# Mutatio_REV1.net
KiCad netlist of a schematic drawn in EAGLE
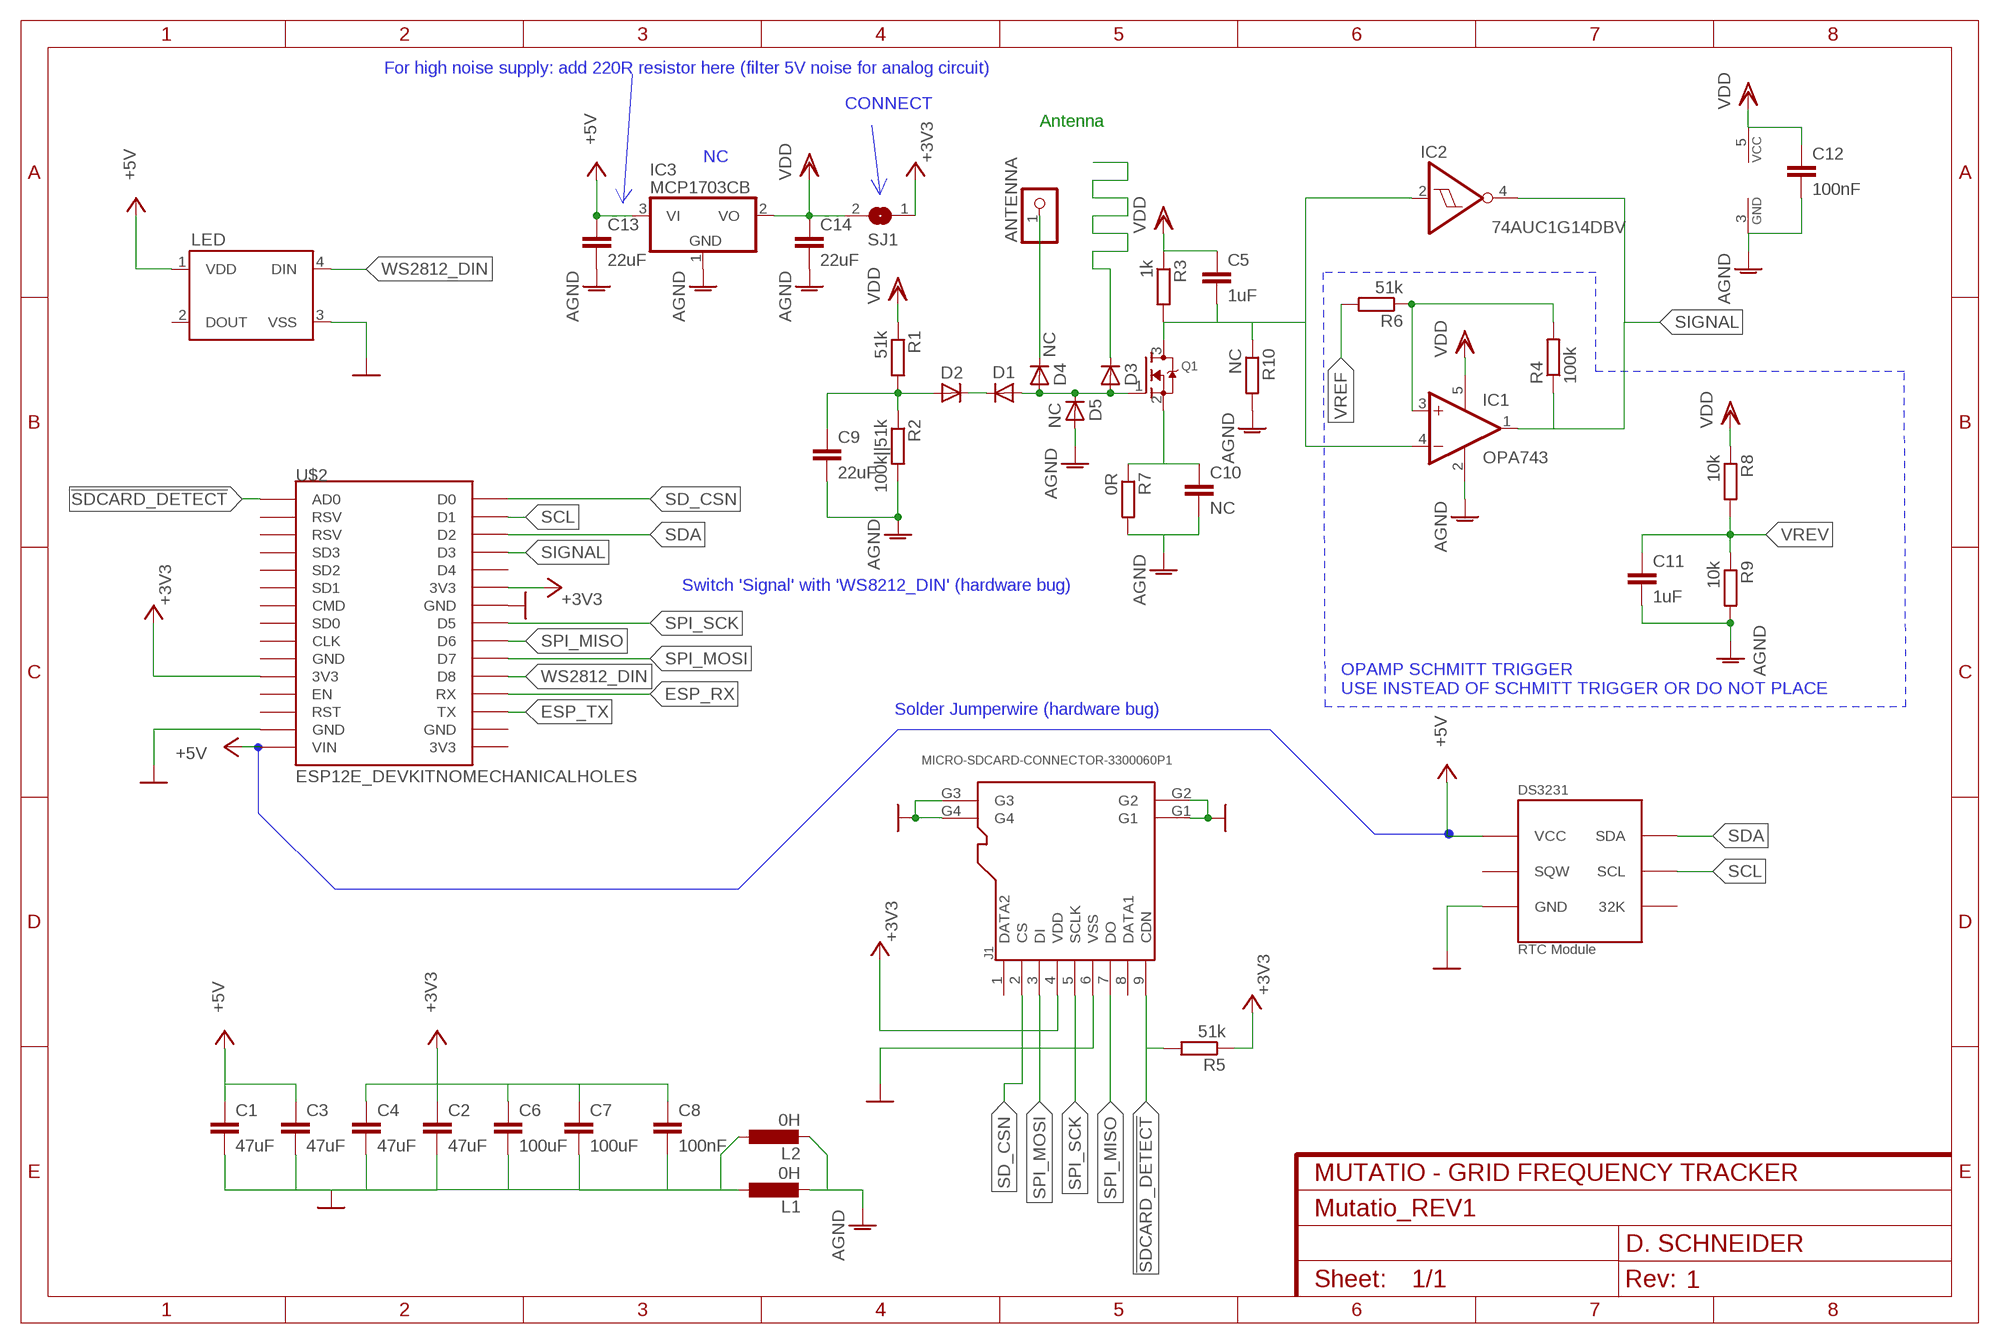
[diagram p0: schematic, sheet 1]

(export (version "E")
  (design (tool "Eeschema 10.0.6"))
  (components
    (comp (ref "ANTENNA")
      (value "PINHD-1X1CB")
      (footprint "eagle-import:1X01-CLEANBIG")
      (libsource (lib "eagle-import") (part "PINHD-1X1CB"))
    )
    (comp (ref "C1")
      (value "47uF")
      (footprint "eagle-import:C0805")
      (libsource (lib "eagle-import") (part "C-EUC0805"))
    )
    (comp (ref "C2")
      (value "47uF")
      (footprint "eagle-import:C0805")
      (libsource (lib "eagle-import") (part "C-EUC0805"))
    )
    (comp (ref "C3")
      (value "47uF")
      (footprint "eagle-import:C0805")
      (libsource (lib "eagle-import") (part "C-EUC0805"))
    )
    (comp (ref "C4")
      (value "47uF")
      (footprint "eagle-import:C0805")
      (libsource (lib "eagle-import") (part "C-EUC0805"))
    )
    (comp (ref "C5")
      (value "1uF")
      (footprint "eagle-import:C0603")
      (libsource (lib "eagle-import") (part "C-EUC0603"))
    )
    (comp (ref "C6")
      (value "100uF")
      (footprint "eagle-import:C1206")
      (libsource (lib "eagle-import") (part "C-EUC1206"))
    )
    (comp (ref "C7")
      (value "100uF")
      (footprint "eagle-import:C1206")
      (libsource (lib "eagle-import") (part "C-EUC1206"))
    )
    (comp (ref "C8")
      (value "100nF")
      (footprint "eagle-import:C0603")
      (libsource (lib "eagle-import") (part "C-EUC0603"))
    )
    (comp (ref "C9")
      (value "22uF")
      (footprint "eagle-import:C0603")
      (libsource (lib "eagle-import") (part "C-EUC0603"))
    )
    (comp (ref "C10")
      (value "NC")
      (footprint "eagle-import:C0603")
      (libsource (lib "eagle-import") (part "C-EUC0603"))
    )
    (comp (ref "C11")
      (value "1uF")
      (footprint "eagle-import:C0603")
      (libsource (lib "eagle-import") (part "C-EUC0603"))
    )
    (comp (ref "C12")
      (value "100nF")
      (footprint "eagle-import:C0603")
      (libsource (lib "eagle-import") (part "C-EUC0603"))
    )
    (comp (ref "C13")
      (value "22uF")
      (footprint "eagle-import:C0603")
      (libsource (lib "eagle-import") (part "C-EUC0603"))
    )
    (comp (ref "C14")
      (value "22uF")
      (footprint "eagle-import:C0603")
      (libsource (lib "eagle-import") (part "C-EUC0603"))
    )
    (comp (ref "D1")
      (value "DIODE-MINIMELF")
      (footprint "eagle-import:MINIMELF")
      (libsource (lib "eagle-import") (part "DIODE-MINIMELF"))
    )
    (comp (ref "D2")
      (value "DIODE-MINIMELF")
      (footprint "eagle-import:MINIMELF")
      (libsource (lib "eagle-import") (part "DIODE-MINIMELF"))
    )
    (comp (ref "D3")
      (value "DIODE-MINIMELF")
      (footprint "eagle-import:MINIMELF")
      (libsource (lib "eagle-import") (part "DIODE-MINIMELF"))
    )
    (comp (ref "D4")
      (value "NC")
      (footprint "eagle-import:MINIMELF")
      (libsource (lib "eagle-import") (part "DIODE-MINIMELF"))
    )
    (comp (ref "D5")
      (value "NC")
      (footprint "eagle-import:MINIMELF")
      (libsource (lib "eagle-import") (part "DIODE-MINIMELF"))
    )
    (comp (ref "IC1")
      (value "OPA743")
      (footprint "eagle-import:SOT23-5")
      (libsource (lib "eagle-import") (part "OPA743"))
    )
    (comp (ref "IC2")
      (value "74AUC1G14DBV")
      (footprint "eagle-import:SOT23-5")
      (libsource (lib "eagle-import") (part "741G14DBVAUC"))
    )
    (comp (ref "IC3")
      (value "MCP1703CB")
      (footprint "eagle-import:SOT23")
      (libsource (lib "eagle-import") (part "MCP1703CB"))
    )
    (comp (ref "J1")
      (value "MICRO-SDCARD-CONNECTOR-3300060P1")
      (footprint "eagle-import:9P-SMD-W-RING")
      (libsource (lib "eagle-import") (part "MICRO-SDCARD-CONNECTOR-3300060P1"))
    )
    (comp (ref "L1")
      (value "0H")
      (footprint "eagle-import:L2012C")
      (libsource (lib "eagle-import") (part "L-EUL2012C"))
    )
    (comp (ref "L2")
      (value "0H")
      (footprint "eagle-import:L2012C")
      (libsource (lib "eagle-import") (part "L-EUL2012C"))
    )
    (comp (ref "LED")
      (value "WS2812B")
      (footprint "eagle-import:WS2812B")
      (libsource (lib "eagle-import") (part "WS2812B"))
    )
    (comp (ref "Q1")
      (value "MOSFET-NREFLOW")
      (footprint "eagle-import:SOT23")
      (libsource (lib "eagle-import") (part "MOSFET-NREFLOW"))
    )
    (comp (ref "R1")
      (value "51k")
      (footprint "eagle-import:R0603")
      (libsource (lib "eagle-import") (part "R-EU_R0603"))
    )
    (comp (ref "R2")
      (value "100k||51k")
      (footprint "eagle-import:R0603")
      (libsource (lib "eagle-import") (part "R-EU_R0603"))
    )
    (comp (ref "R3")
      (value "1k")
      (footprint "eagle-import:R0603")
      (libsource (lib "eagle-import") (part "R-EU_R0603"))
    )
    (comp (ref "R4")
      (value "100k")
      (footprint "eagle-import:R0603")
      (libsource (lib "eagle-import") (part "R-EU_R0603"))
    )
    (comp (ref "R5")
      (value "51k")
      (footprint "eagle-import:R0603")
      (libsource (lib "eagle-import") (part "R-EU_R0603"))
    )
    (comp (ref "R6")
      (value "51k")
      (footprint "eagle-import:R0603")
      (libsource (lib "eagle-import") (part "R-EU_R0603"))
    )
    (comp (ref "R7")
      (value "0R")
      (footprint "eagle-import:R0603")
      (libsource (lib "eagle-import") (part "R-EU_R0603"))
    )
    (comp (ref "R8")
      (value "10k")
      (footprint "eagle-import:R0603")
      (libsource (lib "eagle-import") (part "R-EU_R0603"))
    )
    (comp (ref "R9")
      (value "10k")
      (footprint "eagle-import:R0603")
      (libsource (lib "eagle-import") (part "R-EU_R0603"))
    )
    (comp (ref "R10")
      (value "NC")
      (footprint "eagle-import:R0603")
      (libsource (lib "eagle-import") (part "R-EU_R0603"))
    )
    (comp (ref "SJ1") (value "SJ") (footprint "eagle-import:SJ") (libsource (lib "eagle-import") (part "SJ")))
    (comp (ref "U$1")
      (value "DS3231_MODULEBIG_CONNECTER_ONLY")
      (footprint "eagle-import:DS3231_MODULE_BIGCON")
      (libsource (lib "eagle-import") (part "DS3231_MODULEBIG_CONNECTER_ONLY"))
    )
    (comp (ref "U$2")
      (value "ESP12E_DEVKITNOMECHANICALHOLES")
      (footprint "eagle-import:ESP12E_DEVKIT_NOHOLES")
      (libsource (lib "eagle-import") (part "ESP12E_DEVKITNOMECHANICALHOLES"))
    )
  )
  (nets
    (net (code "1") (name "+3V3") (class "Default")
      (node (ref "C2") (pin "1") (pinfunction "1_1") (pintype "passive"))
      (node (ref "C4") (pin "1") (pinfunction "1_1") (pintype "passive"))
      (node (ref "C6") (pin "1") (pinfunction "1_1") (pintype "passive"))
      (node (ref "C7") (pin "1") (pinfunction "1_1") (pintype "passive"))
      (node (ref "C8") (pin "1") (pinfunction "1_1") (pintype "passive"))
      (node (ref "J1") (pin "4") (pinfunction "VDD_4") (pintype "bidirectional"))
      (node (ref "R5") (pin "1") (pinfunction "1_1") (pintype "passive"))
      (node (ref "SJ1") (pin "1") (pinfunction "1_1") (pintype "passive"))
      (node (ref "U$2") (pin "3V3@0") (pinfunction "3V3_3V3@0") (pintype "bidirectional"))
      (node (ref "U$2") (pin "3V3@1") (pinfunction "3V3_3V3@1") (pintype "bidirectional"))
    )
    (net (code "2") (name "+5V") (class "Default")
      (node (ref "C1") (pin "1") (pinfunction "1_1") (pintype "passive"))
      (node (ref "C13") (pin "1") (pinfunction "1_1") (pintype "passive"))
      (node (ref "C3") (pin "1") (pinfunction "1_1") (pintype "passive"))
      (node (ref "IC3") (pin "3") (pinfunction "VI_3") (pintype "input"))
      (node (ref "LED") (pin "1") (pinfunction "VDD_1") (pintype "power_in"))
      (node (ref "U$1") (pin "VCC@2") (pinfunction "VCC_VCC@2") (pintype "bidirectional"))
      (node (ref "U$2") (pin "VIN") (pinfunction "VIN_VIN") (pintype "bidirectional"))
    )
    (net (code "3") (name "/~{SDCARD_DETECT}") (class "Default")
      (node (ref "J1") (pin "9") (pinfunction "CDN_9") (pintype "bidirectional"))
      (node (ref "R5") (pin "2") (pinfunction "2_2") (pintype "passive"))
      (node (ref "U$2") (pin "AD0") (pinfunction "AD0_AD0") (pintype "bidirectional"))
    )
    (net (code "4") (name "AGND") (class "Default")
      (node (ref "C10") (pin "2") (pinfunction "2_2") (pintype "passive"))
      (node (ref "C11") (pin "2") (pinfunction "2_2") (pintype "passive"))
      (node (ref "C12") (pin "2") (pinfunction "2_2") (pintype "passive"))
      (node (ref "C13") (pin "2") (pinfunction "2_2") (pintype "passive"))
      (node (ref "C14") (pin "2") (pinfunction "2_2") (pintype "passive"))
      (node (ref "C9") (pin "2") (pinfunction "2_2") (pintype "passive"))
      (node (ref "D5") (pin "A") (pinfunction "A_A") (pintype "passive"))
      (node (ref "IC1") (pin "2") (pinfunction "V-_2") (pintype "power_in"))
      (node (ref "IC2") (pin "3") (pinfunction "GND_3") (pintype "power_in"))
      (node (ref "IC3") (pin "1") (pinfunction "GND_1") (pintype "passive"))
      (node (ref "L1") (pin "2") (pinfunction "2_2") (pintype "passive"))
      (node (ref "L2") (pin "2") (pinfunction "2_2") (pintype "passive"))
      (node (ref "R10") (pin "2") (pinfunction "2_2") (pintype "passive"))
      (node (ref "R2") (pin "2") (pinfunction "2_2") (pintype "passive"))
      (node (ref "R7") (pin "2") (pinfunction "2_2") (pintype "passive"))
      (node (ref "R9") (pin "2") (pinfunction "2_2") (pintype "passive"))
    )
    (net (code "5") (name "ESP_RX") (class "Default")
      (node (ref "U$2") (pin "RX") (pinfunction "RX_RX") (pintype "bidirectional"))
    )
    (net (code "6") (name "ESP_TX") (class "Default")
      (node (ref "U$2") (pin "TX") (pinfunction "TX_TX") (pintype "bidirectional"))
    )
    (net (code "7") (name "GND") (class "Default")
      (node (ref "C1") (pin "2") (pinfunction "2_2") (pintype "passive"))
      (node (ref "C2") (pin "2") (pinfunction "2_2") (pintype "passive"))
      (node (ref "C3") (pin "2") (pinfunction "2_2") (pintype "passive"))
      (node (ref "C4") (pin "2") (pinfunction "2_2") (pintype "passive"))
      (node (ref "C6") (pin "2") (pinfunction "2_2") (pintype "passive"))
      (node (ref "C7") (pin "2") (pinfunction "2_2") (pintype "passive"))
      (node (ref "C8") (pin "2") (pinfunction "2_2") (pintype "passive"))
      (node (ref "J1") (pin "6") (pinfunction "VSS_6") (pintype "bidirectional"))
      (node (ref "J1") (pin "G1") (pinfunction "G1_G1") (pintype "bidirectional"))
      (node (ref "J1") (pin "G2") (pinfunction "G2_G2") (pintype "bidirectional"))
      (node (ref "J1") (pin "G3") (pinfunction "G3_G3") (pintype "bidirectional"))
      (node (ref "J1") (pin "G4") (pinfunction "G4_G4") (pintype "bidirectional"))
      (node (ref "L1") (pin "1") (pinfunction "1_1") (pintype "passive"))
      (node (ref "L2") (pin "1") (pinfunction "1_1") (pintype "passive"))
      (node (ref "LED") (pin "3") (pinfunction "VSS_3") (pintype "power_in"))
      (node (ref "U$1") (pin "GND@2") (pinfunction "GND_GND@2") (pintype "bidirectional"))
      (node (ref "U$2") (pin "GND@1") (pinfunction "GND_GND@1") (pintype "bidirectional"))
      (node (ref "U$2") (pin "GND@2") (pinfunction "GND_GND@2") (pintype "bidirectional"))
    )
    (net (code "8") (name "Net-(ANTENNA-Pad1)") (class "Default")
      (node (ref "ANTENNA") (pin "1") (pinfunction "1_1") (pintype "passive"))
      (node (ref "D4") (pin "C") (pinfunction "C_C") (pintype "passive"))
    )
    (net (code "9") (name "Net-(C9-Pad1)") (class "Default")
      (node (ref "C9") (pin "1") (pinfunction "1_1") (pintype "passive"))
      (node (ref "D2") (pin "A") (pinfunction "A_A") (pintype "passive"))
      (node (ref "R1") (pin "2") (pinfunction "2_2") (pintype "passive"))
      (node (ref "R2") (pin "1") (pinfunction "1_1") (pintype "passive"))
    )
    (net (code "10") (name "Net-(D1-PadC)") (class "Default")
      (node (ref "D1") (pin "C") (pinfunction "C_C") (pintype "passive"))
      (node (ref "D2") (pin "C") (pinfunction "C_C") (pintype "passive"))
    )
    (net (code "11") (name "Net-(IC1-+IN)") (class "Default")
      (node (ref "IC1") (pin "3") (pinfunction "+IN_3") (pintype "input"))
      (node (ref "R4") (pin "2") (pinfunction "2_2") (pintype "passive"))
      (node (ref "R6") (pin "1") (pinfunction "1_1") (pintype "passive"))
    )
    (net (code "12") (name "Net-(IC1--IN)") (class "Default")
      (node (ref "C5") (pin "2") (pinfunction "2_2") (pintype "passive"))
      (node (ref "IC1") (pin "4") (pinfunction "-IN_4") (pintype "input"))
      (node (ref "IC2") (pin "2") (pinfunction "I_2") (pintype "input"))
      (node (ref "Q1") (pin "3") (pinfunction "D_3") (pintype "bidirectional"))
      (node (ref "R10") (pin "1") (pinfunction "1_1") (pintype "passive"))
      (node (ref "R3") (pin "2") (pinfunction "2_2") (pintype "passive"))
    )
    (net (code "13") (name "Net-(Q1-G)") (class "Default")
      (node (ref "D1") (pin "A") (pinfunction "A_A") (pintype "passive"))
      (node (ref "D3") (pin "A") (pinfunction "A_A") (pintype "passive"))
      (node (ref "D4") (pin "A") (pinfunction "A_A") (pintype "passive"))
      (node (ref "D5") (pin "C") (pinfunction "C_C") (pintype "passive"))
      (node (ref "Q1") (pin "1") (pinfunction "G_1") (pintype "bidirectional"))
    )
    (net (code "14") (name "Net-(Q1-S)") (class "Default")
      (node (ref "C10") (pin "1") (pinfunction "1_1") (pintype "passive"))
      (node (ref "Q1") (pin "2") (pinfunction "S_2") (pintype "bidirectional"))
      (node (ref "R7") (pin "1") (pinfunction "1_1") (pintype "passive"))
    )
    (net (code "15") (name "SCL") (class "Default")
      (node (ref "U$1") (pin "SCL@2") (pinfunction "SCL_SCL@2") (pintype "bidirectional"))
      (node (ref "U$2") (pin "D1") (pinfunction "D1_D1") (pintype "bidirectional"))
    )
    (net (code "16") (name "SDA") (class "Default")
      (node (ref "U$1") (pin "SDA@2") (pinfunction "SDA_SDA@2") (pintype "bidirectional"))
      (node (ref "U$2") (pin "D2") (pinfunction "D2_D2") (pintype "bidirectional"))
    )
    (net (code "17") (name "SD_CSN") (class "Default")
      (node (ref "J1") (pin "2") (pinfunction "CS_2") (pintype "bidirectional"))
      (node (ref "U$2") (pin "D0") (pinfunction "D0_D0") (pintype "bidirectional"))
    )
    (net (code "18") (name "SIGNAL") (class "Default")
      (node (ref "IC1") (pin "1") (pinfunction "OUT_1") (pintype "output"))
      (node (ref "IC2") (pin "4") (pinfunction "O_4") (pintype "output"))
      (node (ref "R4") (pin "1") (pinfunction "1_1") (pintype "passive"))
      (node (ref "U$2") (pin "D3") (pinfunction "D3_D3") (pintype "bidirectional"))
    )
    (net (code "19") (name "SPI_MISO") (class "Default")
      (node (ref "J1") (pin "7") (pinfunction "DO_7") (pintype "bidirectional"))
      (node (ref "U$2") (pin "D6") (pinfunction "D6_D6") (pintype "bidirectional"))
    )
    (net (code "20") (name "SPI_MOSI") (class "Default")
      (node (ref "J1") (pin "3") (pinfunction "DI_3") (pintype "bidirectional"))
      (node (ref "U$2") (pin "D7") (pinfunction "D7_D7") (pintype "bidirectional"))
    )
    (net (code "21") (name "SPI_SCK") (class "Default")
      (node (ref "J1") (pin "5") (pinfunction "SCLK_5") (pintype "bidirectional"))
      (node (ref "U$2") (pin "D5") (pinfunction "D5_D5") (pintype "bidirectional"))
    )
    (net (code "22") (name "VDD") (class "Default")
      (node (ref "C12") (pin "1") (pinfunction "1_1") (pintype "passive"))
      (node (ref "C14") (pin "1") (pinfunction "1_1") (pintype "passive"))
      (node (ref "C5") (pin "1") (pinfunction "1_1") (pintype "passive"))
      (node (ref "IC1") (pin "5") (pinfunction "V+_5") (pintype "power_in"))
      (node (ref "IC2") (pin "5") (pinfunction "VCC_5") (pintype "power_in"))
      (node (ref "IC3") (pin "2") (pinfunction "VO_2") (pintype "passive"))
      (node (ref "R1") (pin "1") (pinfunction "1_1") (pintype "passive"))
      (node (ref "R3") (pin "1") (pinfunction "1_1") (pintype "passive"))
      (node (ref "R8") (pin "1") (pinfunction "1_1") (pintype "passive"))
      (node (ref "SJ1") (pin "2") (pinfunction "2_2") (pintype "passive"))
    )
    (net (code "23") (name "VREF") (class "Default")
      (node (ref "R6") (pin "2") (pinfunction "2_2") (pintype "passive"))
    )
    (net (code "24") (name "VREV") (class "Default")
      (node (ref "C11") (pin "1") (pinfunction "1_1") (pintype "passive"))
      (node (ref "R8") (pin "2") (pinfunction "2_2") (pintype "passive"))
      (node (ref "R9") (pin "1") (pinfunction "1_1") (pintype "passive"))
    )
    (net (code "25") (name "WS2812_DIN") (class "Default")
      (node (ref "LED") (pin "4") (pinfunction "DIN_4") (pintype "input"))
      (node (ref "U$2") (pin "D8") (pinfunction "D8_D8") (pintype "bidirectional"))
    )
    (net (code "26") (name "unconnected-(D3-PadC)") (class "Default")
      (node (ref "D3") (pin "C") (pinfunction "C_C") (pintype "passive"))
    )
    (net (code "27") (name "unconnected-(J1-DATA1-Pad8)") (class "Default")
      (node (ref "J1") (pin "8") (pinfunction "DATA1_8") (pintype "bidirectional"))
    )
    (net (code "28") (name "unconnected-(J1-DATA2-Pad1)") (class "Default")
      (node (ref "J1") (pin "1") (pinfunction "DATA2_1") (pintype "bidirectional"))
    )
    (net (code "29") (name "unconnected-(LED-DOUT-Pad2)") (class "Default")
      (node (ref "LED") (pin "2") (pinfunction "DOUT_2") (pintype "output"))
    )
    (net (code "30") (name "unconnected-(U$1-Pad32K)") (class "Default")
      (node (ref "U$1") (pin "32K") (pinfunction "32K_32K") (pintype "bidirectional"))
    )
    (net (code "31") (name "unconnected-(U$1-PadSQW)") (class "Default")
      (node (ref "U$1") (pin "SQW") (pinfunction "SQW_SQW") (pintype "bidirectional"))
    )
    (net (code "32") (name "unconnected-(U$2-3V3-Pad3V3@2)") (class "Default")
      (node (ref "U$2") (pin "3V3@2") (pinfunction "3V3_3V3@2") (pintype "bidirectional"))
    )
    (net (code "33") (name "unconnected-(U$2-GND-PadGND@0)") (class "Default")
      (node (ref "U$2") (pin "GND@0") (pinfunction "GND_GND@0") (pintype "bidirectional"))
    )
    (net (code "34") (name "unconnected-(U$2-GND-PadGND@3)") (class "Default")
      (node (ref "U$2") (pin "GND@3") (pinfunction "GND_GND@3") (pintype "bidirectional"))
    )
    (net (code "35") (name "unconnected-(U$2-PadCLK)") (class "Default")
      (node (ref "U$2") (pin "CLK") (pinfunction "CLK_CLK") (pintype "bidirectional"))
    )
    (net (code "36") (name "unconnected-(U$2-PadCMD)") (class "Default")
      (node (ref "U$2") (pin "CMD") (pinfunction "CMD_CMD") (pintype "bidirectional"))
    )
    (net (code "37") (name "unconnected-(U$2-PadD4)") (class "Default")
      (node (ref "U$2") (pin "D4") (pinfunction "D4_D4") (pintype "bidirectional"))
    )
    (net (code "38") (name "unconnected-(U$2-PadEN)") (class "Default")
      (node (ref "U$2") (pin "EN") (pinfunction "EN_EN") (pintype "bidirectional"))
    )
    (net (code "39") (name "unconnected-(U$2-PadRST)") (class "Default")
      (node (ref "U$2") (pin "RST") (pinfunction "RST_RST") (pintype "bidirectional"))
    )
    (net (code "40") (name "unconnected-(U$2-PadSD0)") (class "Default")
      (node (ref "U$2") (pin "SD0") (pinfunction "SD0_SD0") (pintype "bidirectional"))
    )
    (net (code "41") (name "unconnected-(U$2-PadSD1)") (class "Default")
      (node (ref "U$2") (pin "SD1") (pinfunction "SD1_SD1") (pintype "bidirectional"))
    )
    (net (code "42") (name "unconnected-(U$2-PadSD2)") (class "Default")
      (node (ref "U$2") (pin "SD2") (pinfunction "SD2_SD2") (pintype "bidirectional"))
    )
    (net (code "43") (name "unconnected-(U$2-PadSD3)") (class "Default")
      (node (ref "U$2") (pin "SD3") (pinfunction "SD3_SD3") (pintype "bidirectional"))
    )
    (net (code "44") (name "unconnected-(U$2-RSV-PadRSV@0)") (class "Default")
      (node (ref "U$2") (pin "RSV@0") (pinfunction "RSV_RSV@0") (pintype "bidirectional"))
    )
    (net (code "45") (name "unconnected-(U$2-RSV-PadRSV@1)") (class "Default")
      (node (ref "U$2") (pin "RSV@1") (pinfunction "RSV_RSV@1") (pintype "bidirectional"))
    )
  )
)
